# YW_001.net
KiCad netlist of a schematic drawn in Altium Designer
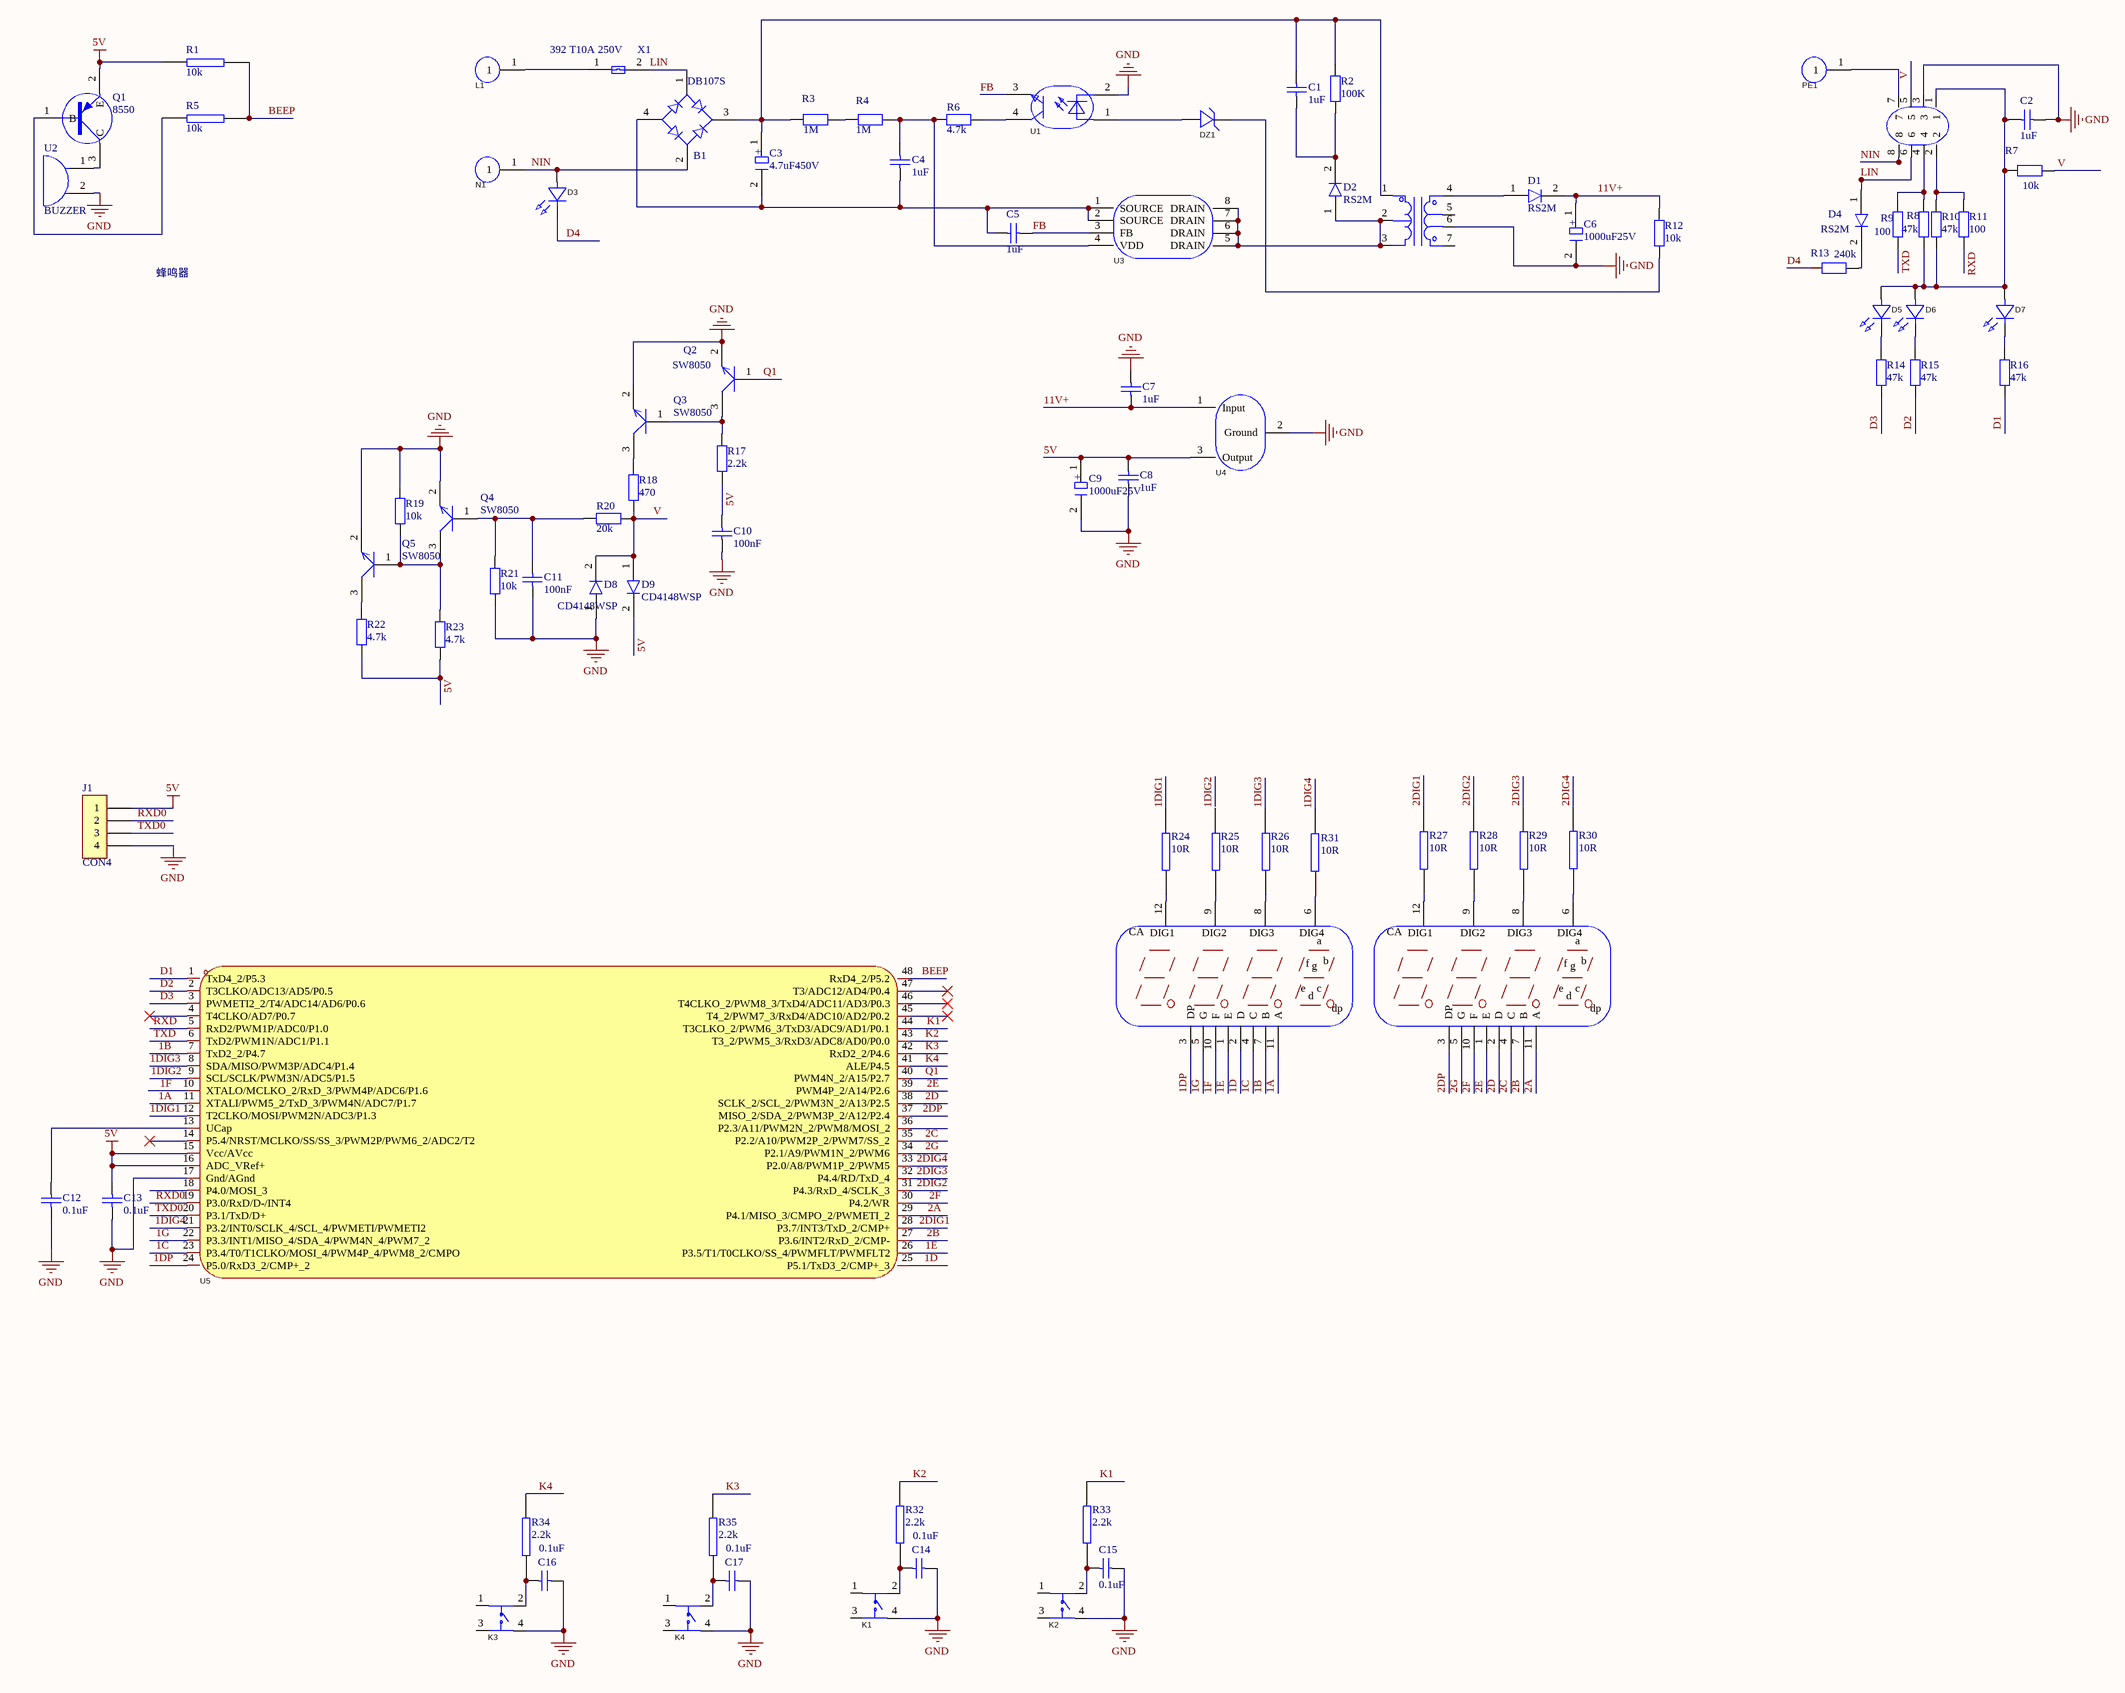
[diagram p0: YW_001.SchDoc]

(export (version "E")
  (design (tool "Eeschema 10.0.6"))
  (components
    (comp (ref "B1") (value "DB107S") (footprint "DB107S") (libsource (lib "*") (part "整流桥堆")))
    (comp (ref "C1")
      (value "1uF")
      (footprint "CAP-TH_L5.5-W4.0-P5.00-D0.5")
      (description "Capacitor")
      (fields (field (name "PUBLISHER") "Altium Limited"))
      (libsource (lib "*") (part "Cap"))
    )
    (comp (ref "C2")
      (value "1uF")
      (footprint "0805C")
      (description "Capacitor")
      (fields (field (name "PUBLISHER") "Altium Limited"))
      (libsource (lib "*") (part "Cap"))
    )
    (comp (ref "C3")
      (value "4.7uF450V")
      (footprint "CAP-TH_BD6.3-P2.50-D1.0-FD")
      (libsource (lib "*") (part "电解电容"))
    )
    (comp (ref "C4")
      (value "1uF")
      (footprint "0805C")
      (description "Capacitor")
      (fields (field (name "PUBLISHER") "Altium Limited"))
      (libsource (lib "*") (part "Cap"))
    )
    (comp (ref "C5")
      (value "1uF")
      (footprint "0805C")
      (description "Capacitor")
      (fields (field (name "PUBLISHER") "Altium Limited"))
      (libsource (lib "*") (part "Cap"))
    )
    (comp (ref "C6")
      (value "1000uF25V")
      (footprint "CAP-TH_BD10.0-P5.00-D1.0-FD")
      (description "CD2881081EM1017VFL")
      (libsource (lib "*") (part "电解电容"))
    )
    (comp (ref "C7")
      (value "1uF")
      (footprint "0805C")
      (description "Capacitor")
      (fields (field (name "PUBLISHER") "Altium Limited"))
      (libsource (lib "*") (part "Cap"))
    )
    (comp (ref "C8")
      (value "1uF")
      (footprint "0805C")
      (description "Capacitor")
      (fields (field (name "PUBLISHER") "Altium Limited"))
      (libsource (lib "*") (part "Cap"))
    )
    (comp (ref "C9")
      (value "1000uF25V")
      (footprint "CAP-TH_BD10.0-P5.00-D1.0-FD")
      (description "CD2881081EM1017VFL")
      (libsource (lib "*") (part "电解电容"))
    )
    (comp (ref "C10")
      (value "100nF")
      (footprint "0805C")
      (description "Capacitor")
      (fields (field (name "PUBLISHER") "Altium Limited"))
      (libsource (lib "*") (part "Cap"))
    )
    (comp (ref "C11")
      (value "100nF")
      (footprint "0805C")
      (description "Capacitor")
      (fields (field (name "PUBLISHER") "Altium Limited"))
      (libsource (lib "*") (part "Cap"))
    )
    (comp (ref "C12")
      (value "0.1uF")
      (footprint "C0603")
      (description "Capacitor")
      (fields (field (name "Comment") "100nF") (field (name "PUBLISHER") "Altium Limited"))
      (libsource (lib "*") (part "Cap"))
    )
    (comp (ref "C13")
      (value "0.1uF")
      (footprint "C0603")
      (description "Capacitor")
      (fields (field (name "Comment") "100nF") (field (name "PUBLISHER") "Altium Limited"))
      (libsource (lib "*") (part "Cap"))
    )
    (comp (ref "C14")
      (value "0.1uF")
      (footprint "0805C")
      (description "Capacitor")
      (fields (field (name "Comment") "104P") (field (name "PUBLISHER") "Altium Limited"))
      (libsource (lib "*") (part "Cap"))
    )
    (comp (ref "C15")
      (value "0.1uF")
      (footprint "0805C")
      (description "Capacitor")
      (fields (field (name "Comment") "104P") (field (name "PUBLISHER") "Altium Limited"))
      (libsource (lib "*") (part "Cap"))
    )
    (comp (ref "C16")
      (value "0.1uF")
      (footprint "0805C")
      (description "Capacitor")
      (fields (field (name "Comment") "104P") (field (name "PUBLISHER") "Altium Limited"))
      (libsource (lib "*") (part "Cap"))
    )
    (comp (ref "C17")
      (value "0.1uF")
      (footprint "0805C")
      (description "Capacitor")
      (fields (field (name "Comment") "104P") (field (name "PUBLISHER") "Altium Limited"))
      (libsource (lib "*") (part "Cap"))
    )
    (comp (ref "D1")
      (value "RS2M")
      (footprint "SMA-SMD_L4.4-W2.7-LS5.4-RD")
      (libsource (lib "CAMERON") (part "二极管"))
    )
    (comp (ref "D2")
      (value "RS2M")
      (footprint "SMA-SMD_L4.4-W2.7-LS5.4-RD")
      (libsource (lib "CAMERON") (part "二极管"))
    )
    (comp (ref "D3")
      (value "HLMP-1503-D0000")
      (footprint "LED-TH_BD3.0-P2.54-RD")
      (fields (field (name "MANUFACTURER") "Broadcom/AVAGO(安华高)"))
      (libsource (lib "CAMERON") (part "HLMP-1503-D0000"))
    )
    (comp (ref "D4")
      (value "RS2M")
      (footprint "SMA-SMD_L4.4-W2.7-LS5.4-RD")
      (libsource (lib "CAMERON") (part "二极管"))
    )
    (comp (ref "D5")
      (value "HLMP-1503-D0000")
      (footprint "LED-TH_BD3.0-P2.54-RD")
      (fields (field (name "MANUFACTURER") "Broadcom/AVAGO(安华高)"))
      (libsource (lib "CAMERON") (part "HLMP-1503-D0000"))
    )
    (comp (ref "D6")
      (value "HLMP-1503-D0000")
      (footprint "LED-TH_BD3.0-P2.54-RD")
      (fields (field (name "MANUFACTURER") "Broadcom/AVAGO(安华高)"))
      (libsource (lib "CAMERON") (part "HLMP-1503-D0000"))
    )
    (comp (ref "D7")
      (value "HLMP-1503-D0000")
      (footprint "LED-TH_BD3.0-P2.54-RD")
      (fields (field (name "MANUFACTURER") "Broadcom/AVAGO(安华高)"))
      (libsource (lib "CAMERON") (part "HLMP-1503-D0000"))
    )
    (comp (ref "D8") (value "CD4148WSP") (footprint "D0805-RD") (libsource (lib "CAMERON") (part "二极管")))
    (comp (ref "D9") (value "CD4148WSP") (footprint "D0805-RD") (libsource (lib "CAMERON") (part "二极管")))
    (comp (ref "DZ1")
      (value "ZMM24")
      (footprint "LL-34_L3.5-W1.5-RD")
      (fields (field (name "MANUFACTURER") "HXY MOSFET(华轩阳电子)"))
      (libsource (lib "CAMERON") (part "ZMM24_C7470923"))
    )
    (comp (ref "H1")
      (value "HC-5557-2*4AW")
      (footprint "CONN-TH_8P-P4.20_5557-2X4AW")
      (fields (field (name "MANUFACTURER") "HCTL(华灿天禄)"))
      (libsource (lib "CAMERON") (part "HC-5557-2*4AW"))
    )
    (comp (ref "J1")
      (value "CON4")
      (footprint "HDR1X4")
      (description "Connector")
      (libsource (lib "*") (part "CON4"))
    )
    (comp (ref "K1")
      (value "TS1212TPFS 250gf 072")
      (footprint "KEY-SMD_4P-L12.0-W12.0-P5.00-LS15.0")
      (fields (field (name "MANUFACTURER") "SHOU HAN(首韩)"))
      (libsource (lib "CAMERON") (part "TS1212TPFS 250gf 072"))
    )
    (comp (ref "K2")
      (value "TS1212TPFS 250gf 072")
      (footprint "KEY-SMD_4P-L12.0-W12.0-P5.00-LS15.0")
      (fields (field (name "MANUFACTURER") "SHOU HAN(首韩)"))
      (libsource (lib "CAMERON") (part "TS1212TPFS 250gf 072"))
    )
    (comp (ref "K3")
      (value "TS1212TPFS 250gf 072")
      (footprint "KEY-SMD_4P-L12.0-W12.0-P5.00-LS15.0")
      (fields (field (name "MANUFACTURER") "SHOU HAN(首韩)"))
      (libsource (lib "CAMERON") (part "TS1212TPFS 250gf 072"))
    )
    (comp (ref "K4")
      (value "TS1212TPFS 250gf 072")
      (footprint "KEY-SMD_4P-L12.0-W12.0-P5.00-LS15.0")
      (fields (field (name "MANUFACTURER") "SHOU HAN(首韩)"))
      (libsource (lib "CAMERON") (part "TS1212TPFS 250gf 072"))
    )
    (comp (ref "L1")
      (value "PZ254V-11-01P")
      (footprint "HDR-TH_1P-P5")
      (fields (field (name "MANUFACTURER") "XFCN(兴飞)"))
      (libsource (lib "CAMERON") (part "PZ254V-11-01P"))
    )
    (comp (ref "LED1")
      (value "FJ5461BH 橙红")
      (footprint "LED-SEG-TH_FJ5461AH")
      (fields (field (name "MANUFACTURER") "志浩"))
      (libsource (lib "CAMERON") (part "FJ5461BH 橙红"))
    )
    (comp (ref "LED2")
      (value "FJ5461BH 橙红")
      (footprint "LED-SEG-TH_FJ5461AH")
      (fields (field (name "MANUFACTURER") "志浩"))
      (libsource (lib "CAMERON") (part "FJ5461BH 橙红"))
    )
    (comp (ref "N1")
      (value "PZ254V-11-01P")
      (footprint "HDR-TH_1P-P5")
      (fields (field (name "MANUFACTURER") "XFCN(兴飞)"))
      (libsource (lib "altium-import") (part "root_2_PZ254V-11-01P_"))
    )
    (comp (ref "PE1")
      (value "PZ254V-11-01P")
      (footprint "HDR-TH_1P-P5")
      (fields (field (name "MANUFACTURER") "XFCN(兴飞)"))
      (libsource (lib "CAMERON") (part "PZ254V-11-01P"))
    )
    (comp (ref "Q1") (value "8550") (footprint "SOT-23") (libsource (lib "*") (part "PNP")))
    (comp (ref "Q2")
      (value "SW8050")
      (footprint "SOT-23 - S8550")
      (libsource (lib "CAMERON") (part "普通三级管（NPN）"))
    )
    (comp (ref "Q3")
      (value "SW8050")
      (footprint "SOT-23 - S8550")
      (libsource (lib "CAMERON") (part "普通三级管（NPN）"))
    )
    (comp (ref "Q4")
      (value "SW8050")
      (footprint "SOT-23 - S8550")
      (libsource (lib "CAMERON") (part "普通三级管（NPN）"))
    )
    (comp (ref "Q5")
      (value "SW8050")
      (footprint "SOT-23 - S8550")
      (libsource (lib "CAMERON") (part "普通三级管（NPN）"))
    )
    (comp (ref "R1") (value "10k") (footprint "0805") (libsource (lib "*") (part "RES2")))
    (comp (ref "R2")
      (value "100K")
      (footprint "0805")
      (description "Resistor")
      (fields (field (name "Comment") "100k") (field (name "PUBLISHER") "Altium Limited"))
      (libsource (lib "*") (part "Res2"))
    )
    (comp (ref "R3")
      (value "1M")
      (footprint "0805")
      (description "Resistor")
      (fields (field (name "PUBLISHER") "Altium Limited"))
      (libsource (lib "") (part "Res2_1"))
    )
    (comp (ref "R4")
      (value "1M")
      (footprint "0805")
      (description "Resistor")
      (fields (field (name "PUBLISHER") "Altium Limited"))
      (libsource (lib "") (part "Res2_1"))
    )
    (comp (ref "R5") (value "10k") (footprint "0805") (libsource (lib "*") (part "RES2")))
    (comp (ref "R6")
      (value "4.7k")
      (footprint "0805")
      (description "Resistor")
      (fields (field (name "PUBLISHER") "Altium Limited"))
      (libsource (lib "") (part "Res2_1"))
    )
    (comp (ref "R7")
      (value "10k")
      (footprint "0805")
      (description "Resistor")
      (fields (field (name "PUBLISHER") "Altium Limited"))
      (libsource (lib "") (part "Res2_1"))
    )
    (comp (ref "R8")
      (value "47k")
      (footprint "0805")
      (description "Resistor")
      (fields (field (name "PUBLISHER") "Altium Limited"))
      (libsource (lib "*") (part "Res2"))
    )
    (comp (ref "R9")
      (value "100")
      (footprint "0805")
      (description "Resistor")
      (fields (field (name "PUBLISHER") "Altium Limited"))
      (libsource (lib "") (part "Res2_2"))
    )
    (comp (ref "R10")
      (value "47k")
      (footprint "0805")
      (description "Resistor")
      (fields (field (name "PUBLISHER") "Altium Limited"))
      (libsource (lib "*") (part "Res2"))
    )
    (comp (ref "R11")
      (value "100")
      (footprint "0805")
      (description "Resistor")
      (fields (field (name "PUBLISHER") "Altium Limited"))
      (libsource (lib "") (part "Res2_2"))
    )
    (comp (ref "R12")
      (value "10k")
      (footprint "0805")
      (description "Resistor")
      (fields (field (name "PUBLISHER") "Altium Limited"))
      (libsource (lib "*") (part "Res2"))
    )
    (comp (ref "R13")
      (value "240k")
      (footprint "0805")
      (description "Resistor")
      (fields (field (name "PUBLISHER") "Altium Limited"))
      (libsource (lib "") (part "Res2_1"))
    )
    (comp (ref "R14")
      (value "47k")
      (footprint "0805")
      (description "Resistor")
      (fields (field (name "PUBLISHER") "Altium Limited"))
      (libsource (lib "*") (part "Res2"))
    )
    (comp (ref "R15")
      (value "47k")
      (footprint "0805")
      (description "Resistor")
      (fields (field (name "PUBLISHER") "Altium Limited"))
      (libsource (lib "*") (part "Res2"))
    )
    (comp (ref "R16")
      (value "47k")
      (footprint "0805")
      (description "Resistor")
      (fields (field (name "PUBLISHER") "Altium Limited"))
      (libsource (lib "*") (part "Res2"))
    )
    (comp (ref "R17")
      (value "2.2k")
      (footprint "0805")
      (description "Resistor")
      (fields (field (name "PUBLISHER") "Altium Limited"))
      (libsource (lib "*") (part "Res2"))
    )
    (comp (ref "R18")
      (value "470")
      (footprint "0805")
      (description "Resistor")
      (fields (field (name "PUBLISHER") "Altium Limited"))
      (libsource (lib "*") (part "Res2"))
    )
    (comp (ref "R19")
      (value "10k")
      (footprint "0805")
      (description "Resistor")
      (fields (field (name "PUBLISHER") "Altium Limited"))
      (libsource (lib "*") (part "Res2"))
    )
    (comp (ref "R20")
      (value "20k")
      (footprint "0805")
      (description "Resistor")
      (fields (field (name "PUBLISHER") "Altium Limited"))
      (libsource (lib "") (part "Res2_3"))
    )
    (comp (ref "R21")
      (value "10k")
      (footprint "0805")
      (description "Resistor")
      (fields (field (name "PUBLISHER") "Altium Limited"))
      (libsource (lib "") (part "Res2_2"))
    )
    (comp (ref "R22")
      (value "4.7k")
      (footprint "0805")
      (description "Resistor")
      (fields (field (name "PUBLISHER") "Altium Limited"))
      (libsource (lib "*") (part "Res2"))
    )
    (comp (ref "R23")
      (value "4.7k")
      (footprint "0805")
      (description "Resistor")
      (fields (field (name "PUBLISHER") "Altium Limited"))
      (libsource (lib "*") (part "Res2"))
    )
    (comp (ref "R24") (value "10R") (footprint "R0603") (libsource (lib "*") (part "RES2")))
    (comp (ref "R25") (value "10R") (footprint "R0603") (libsource (lib "*") (part "RES2")))
    (comp (ref "R26") (value "10R") (footprint "R0603") (libsource (lib "*") (part "RES2")))
    (comp (ref "R27") (value "10R") (footprint "R0603") (libsource (lib "*") (part "RES2")))
    (comp (ref "R28") (value "10R") (footprint "R0603") (libsource (lib "*") (part "RES2")))
    (comp (ref "R29") (value "10R") (footprint "R0603") (libsource (lib "*") (part "RES2")))
    (comp (ref "R30") (value "10R") (footprint "R0603") (libsource (lib "*") (part "RES2")))
    (comp (ref "R31") (value "10R") (footprint "R0603") (libsource (lib "*") (part "RES2")))
    (comp (ref "R32") (value "2.2k") (footprint "0805") (libsource (lib "*") (part "RES2")))
    (comp (ref "R33") (value "2.2k") (footprint "0805") (libsource (lib "*") (part "RES2")))
    (comp (ref "R34") (value "2.2k") (footprint "0805") (libsource (lib "*") (part "RES2")))
    (comp (ref "R35") (value "2.2k") (footprint "0805") (libsource (lib "*") (part "RES2")))
    (comp (ref "U1")
      (value "EL817S1(C)(TU)-F")
      (footprint "OPTO-SMD-4_L4.6-W6.5-P2.54-LS10.3-TL")
      (fields (field (name "MANUFACTURER") "EVERLIGHT(亿光)"))
      (libsource (lib "CAMERON") (part "EL817S1(C)(TU)-F"))
    )
    (comp (ref "U2")
      (value "BUZZER")
      (footprint "BUZZ-7.6/12")
      (description "Buzzer")
      (libsource (lib "*") (part "BUZZER"))
    )
    (comp (ref "U3")
      (value "VIPER12ASTR-E")
      (footprint "SOIC-8_L5.0-W4.0-P1.27-LS6.0-BL")
      (fields (field (name "MANUFACTURER") "ST(意法半导体)"))
      (libsource (lib "CAMERON") (part "VIPER12ASTR-E"))
    )
    (comp (ref "U4")
      (value "MC7805CDTRKG")
      (footprint "TO-252-2_L6.6-W6.1-P4.58-LS9.9-TL")
      (fields (field (name "MANUFACTURER") "onsemi(安森美)"))
      (libsource (lib "CAMERON") (part "MC7805CDTRKG"))
    )
    (comp (ref "U5")
      (value "STC8H8K64U-45I-LQFP48")
      (footprint "LQFP-48_L7.0-W7.0-P0.50-LS9.0-BL")
      (fields (field (name "MANUFACTURER") "STC(宏晶)"))
      (libsource (lib "CAMERON") (part "STC8H8K64U-45I-LQFP48"))
    )
    (comp (ref "USB1")
      (value "ECO2017SEO-X16V015")
      (footprint "XFMR-TH_ECO2017SEO-X16V015")
      (fields (field (name "MANUFACTURER") "TDK"))
      (libsource (lib "CAMERON") (part "ECO2017SEO-X16V015"))
    )
    (comp (ref "X1") (value "392 T10A 250V") (footprint "FUSE") (libsource (lib "*") (part "保险丝")))
  )
  (nets
    (net (code "1") (name "/1A") (class "Default")
      (node (ref "LED1") (pin "11") (pinfunction "A_11") (pintype "passive"))
      (node (ref "U5") (pin "11") (pinfunction "XTALI/PWM5_2/TxD_3/PWM4N/ADC7/P1.7_11") (pintype "passive"))
    )
    (net (code "2") (name "/1B") (class "Default")
      (node (ref "LED1") (pin "7") (pinfunction "B_7") (pintype "passive"))
      (node (ref "U5") (pin "7") (pinfunction "TxD2_2/P4.7_7") (pintype "passive"))
    )
    (net (code "3") (name "/1C") (class "Default")
      (node (ref "LED1") (pin "4") (pinfunction "C_4") (pintype "passive"))
      (node (ref "U5") (pin "23") (pinfunction "P3.4/T0/T1CLKO/MOSI_4/PWM4P_4/PWM8_2/CMPO_23") (pintype "passive"))
    )
    (net (code "4") (name "/1D") (class "Default")
      (node (ref "LED1") (pin "2") (pinfunction "D_2") (pintype "passive"))
      (node (ref "U5") (pin "25") (pinfunction "P5.1/TxD3_2/CMP+_3_25") (pintype "passive"))
    )
    (net (code "5") (name "/1DIG1") (class "Default")
      (node (ref "R24") (pin "1") (pinfunction "1_1") (pintype "passive"))
      (node (ref "U5") (pin "12") (pinfunction "T2CLKO/MOSI/PWM2N/ADC3/P1.3_12") (pintype "passive"))
    )
    (net (code "6") (name "/1DIG2") (class "Default")
      (node (ref "R25") (pin "1") (pinfunction "1_1") (pintype "passive"))
      (node (ref "U5") (pin "9") (pinfunction "SCL/SCLK/PWM3N/ADC5/P1.5_9") (pintype "passive"))
    )
    (net (code "7") (name "/1DIG3") (class "Default")
      (node (ref "R26") (pin "1") (pinfunction "1_1") (pintype "passive"))
      (node (ref "U5") (pin "8") (pinfunction "SDA/MISO/PWM3P/ADC4/P1.4_8") (pintype "passive"))
    )
    (net (code "8") (name "/1DIG4") (class "Default")
      (node (ref "R31") (pin "2") (pinfunction "2_2") (pintype "passive"))
      (node (ref "U5") (pin "21") (pinfunction "P3.2/INT0/SCLK_4/SCL_4/PWMETI/PWMETI2_21") (pintype "passive"))
    )
    (net (code "9") (name "/1DP") (class "Default")
      (node (ref "LED1") (pin "3") (pinfunction "DP_3") (pintype "passive"))
      (node (ref "U5") (pin "24") (pinfunction "P5.0/RxD3_2/CMP+_2_24") (pintype "passive"))
    )
    (net (code "10") (name "/1E") (class "Default")
      (node (ref "LED1") (pin "1") (pinfunction "E_1") (pintype "passive"))
      (node (ref "U5") (pin "26") (pinfunction "P3.5/T1/T0CLKO/SS_4/PWMFLT/PWMFLT2_26") (pintype "passive"))
    )
    (net (code "11") (name "/1F") (class "Default")
      (node (ref "LED1") (pin "10") (pinfunction "F_10") (pintype "passive"))
      (node (ref "U5") (pin "10") (pinfunction "XTALO/MCLKO_2/RxD_3/PWM4P/ADC6/P1.6_10") (pintype "passive"))
    )
    (net (code "12") (name "/1G") (class "Default")
      (node (ref "LED1") (pin "5") (pinfunction "G_5") (pintype "passive"))
      (node (ref "U5") (pin "22") (pinfunction "P3.3/INT1/MISO_4/SDA_4/PWM4N_4/PWM7_2_22") (pintype "passive"))
    )
    (net (code "13") (name "/2A") (class "Default")
      (node (ref "LED2") (pin "11") (pinfunction "A_11") (pintype "passive"))
      (node (ref "U5") (pin "29") (pinfunction "P4.1/MISO_3/CMPO_2/PWMETI_2_29") (pintype "passive"))
    )
    (net (code "14") (name "/2B") (class "Default")
      (node (ref "LED2") (pin "7") (pinfunction "B_7") (pintype "passive"))
      (node (ref "U5") (pin "27") (pinfunction "P3.6/INT2/RxD_2/CMP-_27") (pintype "passive"))
    )
    (net (code "15") (name "/2C") (class "Default")
      (node (ref "LED2") (pin "4") (pinfunction "C_4") (pintype "passive"))
      (node (ref "U5") (pin "35") (pinfunction "P2.2/A10/PWM2P_2/PWM7/SS_2_35") (pintype "passive"))
    )
    (net (code "16") (name "/2D") (class "Default")
      (node (ref "LED2") (pin "2") (pinfunction "D_2") (pintype "passive"))
      (node (ref "U5") (pin "38") (pinfunction "SCLK_2/SCL_2/PWM3N_2/A13/P2.5_38") (pintype "passive"))
    )
    (net (code "17") (name "/2DIG1") (class "Default")
      (node (ref "R27") (pin "1") (pinfunction "1_1") (pintype "passive"))
      (node (ref "U5") (pin "28") (pinfunction "P3.7/INT3/TxD_2/CMP+_28") (pintype "passive"))
    )
    (net (code "18") (name "/2DIG2") (class "Default")
      (node (ref "R28") (pin "1") (pinfunction "1_1") (pintype "passive"))
      (node (ref "U5") (pin "31") (pinfunction "P4.3/RxD_4/SCLK_3_31") (pintype "passive"))
    )
    (net (code "19") (name "/2DIG3") (class "Default")
      (node (ref "R29") (pin "1") (pinfunction "1_1") (pintype "passive"))
      (node (ref "U5") (pin "32") (pinfunction "P4.4/RD/TxD_4_32") (pintype "passive"))
    )
    (net (code "20") (name "/2DIG4") (class "Default")
      (node (ref "R30") (pin "2") (pinfunction "2_2") (pintype "passive"))
      (node (ref "U5") (pin "33") (pinfunction "P2.0/A8/PWM1P_2/PWM5_33") (pintype "passive"))
    )
    (net (code "21") (name "/2DP") (class "Default")
      (node (ref "LED2") (pin "3") (pinfunction "DP_3") (pintype "passive"))
      (node (ref "U5") (pin "37") (pinfunction "MISO_2/SDA_2/PWM3P_2/A12/P2.4_37") (pintype "passive"))
    )
    (net (code "22") (name "/2E") (class "Default")
      (node (ref "LED2") (pin "1") (pinfunction "E_1") (pintype "passive"))
      (node (ref "U5") (pin "39") (pinfunction "PWM4P_2/A14/P2.6_39") (pintype "passive"))
    )
    (net (code "23") (name "/2F") (class "Default")
      (node (ref "LED2") (pin "10") (pinfunction "F_10") (pintype "passive"))
      (node (ref "U5") (pin "30") (pinfunction "P4.2/WR_30") (pintype "passive"))
    )
    (net (code "24") (name "/2G") (class "Default")
      (node (ref "LED2") (pin "5") (pinfunction "G_5") (pintype "passive"))
      (node (ref "U5") (pin "34") (pinfunction "P2.1/A9/PWM1N_2/PWM6_34") (pintype "passive"))
    )
    (net (code "25") (name "/11V+") (class "Default")
      (node (ref "C6") (pin "1") (pintype "passive"))
      (node (ref "C7") (pin "2") (pinfunction "2_2") (pintype "passive"))
      (node (ref "D1") (pin "2") (pintype "passive"))
      (node (ref "R12") (pin "1") (pinfunction "1_1") (pintype "passive"))
      (node (ref "U4") (pin "1") (pinfunction "Input_1") (pintype "passive"))
    )
    (net (code "26") (name "/BEEP") (class "Default")
      (node (ref "R1") (pin "2") (pinfunction "2_2") (pintype "passive"))
      (node (ref "R5") (pin "2") (pinfunction "2_2") (pintype "passive"))
      (node (ref "U5") (pin "48") (pinfunction "RxD4_2/P5.2_48") (pintype "passive"))
    )
    (net (code "27") (name "/D1") (class "Default")
      (node (ref "R16") (pin "2") (pinfunction "2_2") (pintype "passive"))
      (node (ref "U5") (pin "1") (pinfunction "TxD4_2/P5.3_1") (pintype "passive"))
    )
    (net (code "28") (name "/D2") (class "Default")
      (node (ref "R15") (pin "2") (pinfunction "2_2") (pintype "passive"))
      (node (ref "U5") (pin "2") (pinfunction "T3CLKO/ADC13/AD5/P0.5_2") (pintype "passive"))
    )
    (net (code "29") (name "/D3") (class "Default")
      (node (ref "R14") (pin "2") (pinfunction "2_2") (pintype "passive"))
      (node (ref "U5") (pin "3") (pinfunction "PWMETI2_2/T4/ADC14/AD6/P0.6_3") (pintype "passive"))
    )
    (net (code "30") (name "/D4") (class "Default")
      (node (ref "D3") (pin "1") (pinfunction "K_1") (pintype "passive"))
      (node (ref "R13") (pin "2") (pinfunction "2_2") (pintype "passive"))
    )
    (net (code "31") (name "/FB") (class "Default")
      (node (ref "C5") (pin "1") (pinfunction "1_1") (pintype "passive"))
      (node (ref "U1") (pin "3") (pinfunction "EM_3") (pintype "passive"))
      (node (ref "U3") (pin "3") (pinfunction "FB_3") (pintype "passive"))
    )
    (net (code "32") (name "/K1") (class "Default")
      (node (ref "R33") (pin "2") (pinfunction "2_2") (pintype "passive"))
      (node (ref "U5") (pin "44") (pinfunction "T3CLKO_2/PWM6_3/TxD3/ADC9/AD1/P0.1_44") (pintype "passive"))
    )
    (net (code "33") (name "/K2") (class "Default")
      (node (ref "R32") (pin "2") (pinfunction "2_2") (pintype "passive"))
      (node (ref "U5") (pin "43") (pinfunction "T3_2/PWM5_3/RxD3/ADC8/AD0/P0.0_43") (pintype "passive"))
    )
    (net (code "34") (name "/K3") (class "Default")
      (node (ref "R35") (pin "2") (pinfunction "2_2") (pintype "passive"))
      (node (ref "U5") (pin "42") (pinfunction "RxD2_2/P4.6_42") (pintype "passive"))
    )
    (net (code "35") (name "/K4") (class "Default")
      (node (ref "R34") (pin "2") (pinfunction "2_2") (pintype "passive"))
      (node (ref "U5") (pin "41") (pinfunction "ALE/P4.5_41") (pintype "passive"))
    )
    (net (code "36") (name "/LIN") (class "Default")
      (node (ref "B1") (pin "1") (pintype "passive"))
      (node (ref "D4") (pin "1") (pintype "passive"))
      (node (ref "H1") (pin "6") (pinfunction "6_6") (pintype "passive"))
      (node (ref "X1") (pin "2") (pintype "passive"))
    )
    (net (code "37") (name "/NIN") (class "Default")
      (node (ref "B1") (pin "2") (pintype "passive"))
      (node (ref "D3") (pin "2") (pinfunction "A_2") (pintype "passive"))
      (node (ref "H1") (pin "8") (pinfunction "8_8") (pintype "passive"))
      (node (ref "N1") (pin "1") (pinfunction "1_1") (pintype "passive"))
    )
    (net (code "38") (name "/Q1") (class "Default")
      (node (ref "Q2") (pin "1") (pinfunction "B_1") (pintype "passive"))
      (node (ref "U5") (pin "40") (pinfunction "PWM4N_2/A15/P2.7_40") (pintype "passive"))
    )
    (net (code "39") (name "/RXD") (class "Default")
      (node (ref "R11") (pin "1") (pinfunction "1_1") (pintype "passive"))
      (node (ref "U5") (pin "5") (pinfunction "RxD2/PWM1P/ADC0/P1.0_5") (pintype "passive"))
    )
    (net (code "40") (name "/RXD0") (class "Default")
      (node (ref "J1") (pin "2") (pinfunction "2_2") (pintype "passive"))
      (node (ref "U5") (pin "19") (pinfunction "P3.0/RxD/D-/INT4_19") (pintype "passive"))
    )
    (net (code "41") (name "/TXD") (class "Default")
      (node (ref "R9") (pin "1") (pinfunction "1_1") (pintype "passive"))
      (node (ref "U5") (pin "6") (pinfunction "TxD2/PWM1N/ADC1/P1.1_6") (pintype "passive"))
    )
    (net (code "42") (name "/TXD0") (class "Default")
      (node (ref "J1") (pin "3") (pinfunction "3_3") (pintype "passive"))
      (node (ref "U5") (pin "20") (pinfunction "P3.1/TxD/D+_20") (pintype "passive"))
    )
    (net (code "43") (name "/V") (class "Default")
      (node (ref "D8") (pin "2") (pintype "passive"))
      (node (ref "D9") (pin "1") (pintype "passive"))
      (node (ref "H1") (pin "5") (pinfunction "5_5") (pintype "passive"))
      (node (ref "R18") (pin "2") (pinfunction "2_2") (pintype "passive"))
      (node (ref "R20") (pin "2") (pinfunction "2_2") (pintype "passive"))
      (node (ref "R7") (pin "1") (pinfunction "1_1") (pintype "passive"))
    )
    (net (code "44") (name "5V") (class "Default")
      (node (ref "C10") (pin "1") (pinfunction "1_1") (pintype "passive"))
      (node (ref "C13") (pin "2") (pinfunction "2_2") (pintype "passive"))
      (node (ref "C8") (pin "1") (pinfunction "1_1") (pintype "passive"))
      (node (ref "C9") (pin "1") (pintype "passive"))
      (node (ref "D9") (pin "2") (pintype "passive"))
      (node (ref "J1") (pin "1") (pinfunction "1_1") (pintype "passive"))
      (node (ref "Q1") (pin "2") (pinfunction "E_2") (pintype "passive"))
      (node (ref "R1") (pin "1") (pinfunction "1_1") (pintype "passive"))
      (node (ref "R17") (pin "2") (pinfunction "2_2") (pintype "passive"))
      (node (ref "R22") (pin "2") (pinfunction "2_2") (pintype "passive"))
      (node (ref "R23") (pin "2") (pinfunction "2_2") (pintype "passive"))
      (node (ref "U4") (pin "3") (pinfunction "Output_3") (pintype "passive"))
      (node (ref "U5") (pin "15") (pinfunction "Vcc/AVcc_15") (pintype "passive"))
      (node (ref "U5") (pin "16") (pinfunction "ADC_VRef+_16") (pintype "passive"))
    )
    (net (code "45") (name "GND") (class "Default")
      (node (ref "C10") (pin "2") (pinfunction "2_2") (pintype "passive"))
      (node (ref "C11") (pin "2") (pinfunction "2_2") (pintype "passive"))
      (node (ref "C12") (pin "1") (pinfunction "1_1") (pintype "passive"))
      (node (ref "C13") (pin "1") (pinfunction "1_1") (pintype "passive"))
      (node (ref "C14") (pin "2") (pinfunction "2_2") (pintype "passive"))
      (node (ref "C15") (pin "2") (pinfunction "2_2") (pintype "passive"))
      (node (ref "C16") (pin "2") (pinfunction "2_2") (pintype "passive"))
      (node (ref "C17") (pin "2") (pinfunction "2_2") (pintype "passive"))
      (node (ref "C2") (pin "1") (pinfunction "1_1") (pintype "passive"))
      (node (ref "C6") (pin "2") (pintype "passive"))
      (node (ref "C7") (pin "1") (pinfunction "1_1") (pintype "passive"))
      (node (ref "C8") (pin "2") (pinfunction "2_2") (pintype "passive"))
      (node (ref "C9") (pin "2") (pintype "passive"))
      (node (ref "D8") (pin "1") (pintype "passive"))
      (node (ref "H1") (pin "3") (pinfunction "3_3") (pintype "passive"))
      (node (ref "J1") (pin "4") (pinfunction "4_4") (pintype "passive"))
      (node (ref "K1") (pin "4") (pinfunction "4_4") (pintype "passive"))
      (node (ref "K2") (pin "4") (pinfunction "4_4") (pintype "passive"))
      (node (ref "K3") (pin "4") (pinfunction "4_4") (pintype "passive"))
      (node (ref "K4") (pin "4") (pinfunction "4_4") (pintype "passive"))
      (node (ref "Q2") (pin "2") (pinfunction "E_2") (pintype "passive"))
      (node (ref "Q3") (pin "2") (pinfunction "E_2") (pintype "passive"))
      (node (ref "Q4") (pin "2") (pinfunction "E_2") (pintype "passive"))
      (node (ref "Q5") (pin "2") (pinfunction "E_2") (pintype "passive"))
      (node (ref "R19") (pin "1") (pinfunction "1_1") (pintype "passive"))
      (node (ref "R21") (pin "1") (pinfunction "1_1") (pintype "passive"))
      (node (ref "U1") (pin "2") (pinfunction "CAT_2") (pintype "passive"))
      (node (ref "U2") (pin "2") (pinfunction "B_2") (pintype "passive"))
      (node (ref "U4") (pin "2") (pinfunction "Ground_2") (pintype "passive"))
      (node (ref "U5") (pin "17") (pinfunction "Gnd/AGnd_17") (pintype "passive"))
      (node (ref "USB1") (pin "6") (pinfunction "2_6") (pintype "passive"))
    )
    (net (code "46") (name "Net-(B1-Pad4)") (class "Default")
      (node (ref "B1") (pin "4") (pintype "passive"))
      (node (ref "C3") (pin "2") (pintype "passive"))
      (node (ref "C4") (pin "2") (pinfunction "2_2") (pintype "passive"))
      (node (ref "C5") (pin "2") (pinfunction "2_2") (pintype "passive"))
      (node (ref "U3") (pin "1") (pinfunction "SOURCE_1") (pintype "passive"))
      (node (ref "U3") (pin "2") (pinfunction "SOURCE_2") (pintype "passive"))
    )
    (net (code "47") (name "Net-(C1-Pad2)") (class "Default")
      (node (ref "C1") (pin "2") (pinfunction "2_2") (pintype "passive"))
      (node (ref "D2") (pin "2") (pintype "passive"))
      (node (ref "R2") (pin "2") (pinfunction "2_2") (pintype "passive"))
    )
    (net (code "48") (name "Net-(C14-Pad1)") (class "Default")
      (node (ref "C14") (pin "1") (pinfunction "1_1") (pintype "passive"))
      (node (ref "K1") (pin "2") (pinfunction "2_2") (pintype "passive"))
      (node (ref "R32") (pin "1") (pinfunction "1_1") (pintype "passive"))
    )
    (net (code "49") (name "Net-(C15-Pad1)") (class "Default")
      (node (ref "C15") (pin "1") (pinfunction "1_1") (pintype "passive"))
      (node (ref "K2") (pin "2") (pinfunction "2_2") (pintype "passive"))
      (node (ref "R33") (pin "1") (pinfunction "1_1") (pintype "passive"))
    )
    (net (code "50") (name "Net-(C16-Pad1)") (class "Default")
      (node (ref "C16") (pin "1") (pinfunction "1_1") (pintype "passive"))
      (node (ref "K3") (pin "2") (pinfunction "2_2") (pintype "passive"))
      (node (ref "R34") (pin "1") (pinfunction "1_1") (pintype "passive"))
    )
    (net (code "51") (name "Net-(C17-Pad1)") (class "Default")
      (node (ref "C17") (pin "1") (pinfunction "1_1") (pintype "passive"))
      (node (ref "K4") (pin "2") (pinfunction "2_2") (pintype "passive"))
      (node (ref "R35") (pin "1") (pinfunction "1_1") (pintype "passive"))
    )
    (net (code "52") (name "Net-(D4-Pad2)") (class "Default")
      (node (ref "D4") (pin "2") (pintype "passive"))
      (node (ref "R13") (pin "1") (pinfunction "1_1") (pintype "passive"))
    )
    (net (code "53") (name "Net-(D5-A)") (class "Default")
      (node (ref "C2") (pin "2") (pinfunction "2_2") (pintype "passive"))
      (node (ref "D5") (pin "2") (pinfunction "A_2") (pintype "passive"))
      (node (ref "D6") (pin "2") (pinfunction "A_2") (pintype "passive"))
      (node (ref "D7") (pin "2") (pinfunction "A_2") (pintype "passive"))
      (node (ref "H1") (pin "1") (pinfunction "1_1") (pintype "passive"))
      (node (ref "R10") (pin "2") (pinfunction "2_2") (pintype "passive"))
      (node (ref "R7") (pin "2") (pinfunction "2_2") (pintype "passive"))
      (node (ref "R8") (pin "2") (pinfunction "2_2") (pintype "passive"))
    )
    (net (code "54") (name "Net-(D5-K)") (class "Default")
      (node (ref "D5") (pin "1") (pinfunction "K_1") (pintype "passive"))
      (node (ref "R14") (pin "1") (pinfunction "1_1") (pintype "passive"))
    )
    (net (code "55") (name "Net-(D6-K)") (class "Default")
      (node (ref "D6") (pin "1") (pinfunction "K_1") (pintype "passive"))
      (node (ref "R15") (pin "1") (pinfunction "1_1") (pintype "passive"))
    )
    (net (code "56") (name "Net-(D7-K)") (class "Default")
      (node (ref "D7") (pin "1") (pinfunction "K_1") (pintype "passive"))
      (node (ref "R16") (pin "1") (pinfunction "1_1") (pintype "passive"))
    )
    (net (code "57") (name "Net-(DZ1-A)") (class "Default")
      (node (ref "DZ1") (pin "2") (pinfunction "A_2") (pintype "passive"))
      (node (ref "U1") (pin "1") (pinfunction "AN_1") (pintype "passive"))
    )
    (net (code "58") (name "Net-(DZ1-C)") (class "Default")
      (node (ref "DZ1") (pin "1") (pinfunction "C_1") (pintype "passive"))
      (node (ref "R12") (pin "2") (pinfunction "2_2") (pintype "passive"))
    )
    (net (code "59") (name "Net-(H1-Pad2)") (class "Default")
      (node (ref "H1") (pin "2") (pinfunction "2_2") (pintype "passive"))
      (node (ref "R10") (pin "1") (pinfunction "1_1") (pintype "passive"))
      (node (ref "R11") (pin "2") (pinfunction "2_2") (pintype "passive"))
    )
    (net (code "60") (name "Net-(H1-Pad4)") (class "Default")
      (node (ref "H1") (pin "4") (pinfunction "4_4") (pintype "passive"))
      (node (ref "R8") (pin "1") (pinfunction "1_1") (pintype "passive"))
      (node (ref "R9") (pin "2") (pinfunction "2_2") (pintype "passive"))
    )
    (net (code "61") (name "Net-(H1-Pad7)") (class "Default")
      (node (ref "H1") (pin "7") (pinfunction "7_7") (pintype "passive"))
      (node (ref "PE1") (pin "1") (pinfunction "1_1") (pintype "passive"))
    )
    (net (code "62") (name "Net-(L1-Pad1)") (class "Default")
      (node (ref "L1") (pin "1") (pinfunction "1_1") (pintype "passive"))
      (node (ref "X1") (pin "1") (pintype "passive"))
    )
    (net (code "63") (name "Net-(LED1-DIG1)") (class "Default")
      (node (ref "LED1") (pin "12") (pinfunction "DIG1_12") (pintype "passive"))
      (node (ref "R24") (pin "2") (pinfunction "2_2") (pintype "passive"))
    )
    (net (code "64") (name "Net-(LED1-DIG2)") (class "Default")
      (node (ref "LED1") (pin "9") (pinfunction "DIG2_9") (pintype "passive"))
      (node (ref "R25") (pin "2") (pinfunction "2_2") (pintype "passive"))
    )
    (net (code "65") (name "Net-(LED1-DIG3)") (class "Default")
      (node (ref "LED1") (pin "8") (pinfunction "DIG3_8") (pintype "passive"))
      (node (ref "R26") (pin "2") (pinfunction "2_2") (pintype "passive"))
    )
    (net (code "66") (name "Net-(LED1-DIG4)") (class "Default")
      (node (ref "LED1") (pin "6") (pinfunction "DIG4_6") (pintype "passive"))
      (node (ref "R31") (pin "1") (pinfunction "1_1") (pintype "passive"))
    )
    (net (code "67") (name "Net-(LED2-DIG1)") (class "Default")
      (node (ref "LED2") (pin "12") (pinfunction "DIG1_12") (pintype "passive"))
      (node (ref "R27") (pin "2") (pinfunction "2_2") (pintype "passive"))
    )
    (net (code "68") (name "Net-(LED2-DIG2)") (class "Default")
      (node (ref "LED2") (pin "9") (pinfunction "DIG2_9") (pintype "passive"))
      (node (ref "R28") (pin "2") (pinfunction "2_2") (pintype "passive"))
    )
    (net (code "69") (name "Net-(LED2-DIG3)") (class "Default")
      (node (ref "LED2") (pin "8") (pinfunction "DIG3_8") (pintype "passive"))
      (node (ref "R29") (pin "2") (pinfunction "2_2") (pintype "passive"))
    )
    (net (code "70") (name "Net-(LED2-DIG4)") (class "Default")
      (node (ref "LED2") (pin "6") (pinfunction "DIG4_6") (pintype "passive"))
      (node (ref "R30") (pin "1") (pinfunction "1_1") (pintype "passive"))
    )
    (net (code "71") (name "Net-(Q1-B)") (class "Default")
      (node (ref "Q1") (pin "1") (pinfunction "B_1") (pintype "passive"))
      (node (ref "R5") (pin "1") (pinfunction "1_1") (pintype "passive"))
    )
    (net (code "72") (name "Net-(Q1-C)") (class "Default")
      (node (ref "Q1") (pin "3") (pinfunction "C_3") (pintype "passive"))
      (node (ref "U2") (pin "1") (pinfunction "A_1") (pintype "passive"))
    )
    (net (code "73") (name "Net-(Q2-C)") (class "Default")
      (node (ref "Q2") (pin "3") (pinfunction "C_3") (pintype "passive"))
      (node (ref "Q3") (pin "1") (pinfunction "B_1") (pintype "passive"))
      (node (ref "R17") (pin "1") (pinfunction "1_1") (pintype "passive"))
    )
    (net (code "74") (name "Net-(Q3-C)") (class "Default")
      (node (ref "Q3") (pin "3") (pinfunction "C_3") (pintype "passive"))
      (node (ref "R18") (pin "1") (pinfunction "1_1") (pintype "passive"))
    )
    (net (code "75") (name "Net-(Q4-B)") (class "Default")
      (node (ref "C11") (pin "1") (pinfunction "1_1") (pintype "passive"))
      (node (ref "Q4") (pin "1") (pinfunction "B_1") (pintype "passive"))
      (node (ref "R20") (pin "1") (pinfunction "1_1") (pintype "passive"))
      (node (ref "R21") (pin "2") (pinfunction "2_2") (pintype "passive"))
    )
    (net (code "76") (name "Net-(Q4-C)") (class "Default")
      (node (ref "Q4") (pin "3") (pinfunction "C_3") (pintype "passive"))
      (node (ref "Q5") (pin "1") (pinfunction "B_1") (pintype "passive"))
      (node (ref "R19") (pin "2") (pinfunction "2_2") (pintype "passive"))
      (node (ref "R23") (pin "1") (pinfunction "1_1") (pintype "passive"))
    )
    (net (code "77") (name "Net-(Q5-C)") (class "Default")
      (node (ref "Q5") (pin "3") (pinfunction "C_3") (pintype "passive"))
      (node (ref "R22") (pin "1") (pinfunction "1_1") (pintype "passive"))
    )
    (net (code "78") (name "Net-(R3-Pad1)") (class "Default")
      (node (ref "R3") (pin "1") (pinfunction "1_1") (pintype "passive"))
      (node (ref "R4") (pin "2") (pinfunction "2_2") (pintype "passive"))
    )
    (net (code "79") (name "Net-(U1-COL)") (class "Default")
      (node (ref "R6") (pin "1") (pinfunction "1_1") (pintype "passive"))
      (node (ref "U1") (pin "4") (pinfunction "COL_4") (pintype "passive"))
    )
    (net (code "80") (name "Net-(U3-VDD)") (class "Default")
      (node (ref "C4") (pin "1") (pinfunction "1_1") (pintype "passive"))
      (node (ref "R4") (pin "1") (pinfunction "1_1") (pintype "passive"))
      (node (ref "R6") (pin "2") (pinfunction "2_2") (pintype "passive"))
      (node (ref "U3") (pin "4") (pinfunction "VDD_4") (pintype "passive"))
    )
    (net (code "81") (name "Net-(U5-UCap)") (class "Default")
      (node (ref "C12") (pin "2") (pinfunction "2_2") (pintype "passive"))
      (node (ref "U5") (pin "13") (pinfunction "UCap_13") (pintype "passive"))
    )
    (net (code "82") (name "Net-(USB1-5)") (class "Default")
      (node (ref "D1") (pin "1") (pintype "passive"))
      (node (ref "USB1") (pin "4") (pinfunction "5_4") (pintype "passive"))
    )
    (net (code "83") (name "Net-(USB1-9)") (class "Default")
      (node (ref "B1") (pin "3") (pintype "passive"))
      (node (ref "C1") (pin "1") (pinfunction "1_1") (pintype "passive"))
      (node (ref "C3") (pin "1") (pintype "passive"))
      (node (ref "R2") (pin "1") (pinfunction "1_1") (pintype "passive"))
      (node (ref "R3") (pin "2") (pinfunction "2_2") (pintype "passive"))
      (node (ref "USB1") (pin "1") (pinfunction "9_1") (pintype "passive"))
    )
    (net (code "84") (name "Net-(USB1-10)") (class "Default")
      (node (ref "D2") (pin "1") (pintype "passive"))
      (node (ref "U3") (pin "5") (pinfunction "DRAIN_5") (pintype "passive"))
      (node (ref "U3") (pin "6") (pinfunction "DRAIN_6") (pintype "passive"))
      (node (ref "U3") (pin "7") (pinfunction "DRAIN_7") (pintype "passive"))
      (node (ref "U3") (pin "8") (pinfunction "DRAIN_8") (pintype "passive"))
      (node (ref "USB1") (pin "2") (pinfunction "8_2") (pintype "passive"))
      (node (ref "USB1") (pin "3") (pinfunction "10_3") (pintype "passive"))
    )
    (net (code "85") (name "unconnected-(K1-Pad1)") (class "Default")
      (node (ref "K1") (pin "1") (pinfunction "1_1") (pintype "passive"))
    )
    (net (code "86") (name "unconnected-(K1-Pad3)") (class "Default")
      (node (ref "K1") (pin "3") (pinfunction "3_3") (pintype "passive"))
    )
    (net (code "87") (name "unconnected-(K2-Pad1)") (class "Default")
      (node (ref "K2") (pin "1") (pinfunction "1_1") (pintype "passive"))
    )
    (net (code "88") (name "unconnected-(K2-Pad3)") (class "Default")
      (node (ref "K2") (pin "3") (pinfunction "3_3") (pintype "passive"))
    )
    (net (code "89") (name "unconnected-(K3-Pad1)") (class "Default")
      (node (ref "K3") (pin "1") (pinfunction "1_1") (pintype "passive"))
    )
    (net (code "90") (name "unconnected-(K3-Pad3)") (class "Default")
      (node (ref "K3") (pin "3") (pinfunction "3_3") (pintype "passive"))
    )
    (net (code "91") (name "unconnected-(K4-Pad1)") (class "Default")
      (node (ref "K4") (pin "1") (pinfunction "1_1") (pintype "passive"))
    )
    (net (code "92") (name "unconnected-(K4-Pad3)") (class "Default")
      (node (ref "K4") (pin "3") (pinfunction "3_3") (pintype "passive"))
    )
    (net (code "93") (name "unconnected-(U5-P2.3{slash}A11{slash}PWM2N_2{slash}PWM8{slash}MOSI_2-Pad36)") (class "Default")
      (node (ref "U5") (pin "36") (pinfunction "P2.3/A11/PWM2N_2/PWM8/MOSI_2_36") (pintype "passive"))
    )
    (net (code "94") (name "unconnected-(U5-P4.0{slash}MOSI_3-Pad18)") (class "Default")
      (node (ref "U5") (pin "18") (pinfunction "P4.0/MOSI_3_18") (pintype "passive"))
    )
    (net (code "95") (name "unconnected-(U5-P5.4{slash}NRST{slash}MCLKO{slash}SS{slash}SS_3{slash}PWM2P{slash}PWM6_2{slash}ADC2{slash}T2-Pad14)") (class "Default")
      (node (ref "U5") (pin "14") (pinfunction "P5.4/NRST/MCLKO/SS/SS_3/PWM2P/PWM6_2/ADC2/T2_14") (pintype "passive+no_connect"))
    )
    (net (code "96") (name "unconnected-(U5-T3{slash}ADC12{slash}AD4{slash}P0.4-Pad47)") (class "Default")
      (node (ref "U5") (pin "47") (pinfunction "T3/ADC12/AD4/P0.4_47") (pintype "passive+no_connect"))
    )
    (net (code "97") (name "unconnected-(U5-T4CLKO_2{slash}PWM8_3{slash}TxD4{slash}ADC11{slash}AD3{slash}P0.3-Pad46)") (class "Default")
      (node (ref "U5") (pin "46") (pinfunction "T4CLKO_2/PWM8_3/TxD4/ADC11/AD3/P0.3_46") (pintype "passive+no_connect"))
    )
    (net (code "98") (name "unconnected-(U5-T4CLKO{slash}AD7{slash}P0.7-Pad4)") (class "Default")
      (node (ref "U5") (pin "4") (pinfunction "T4CLKO/AD7/P0.7_4") (pintype "passive+no_connect"))
    )
    (net (code "99") (name "unconnected-(U5-T4_2{slash}PWM7_3{slash}RxD4{slash}ADC10{slash}AD2{slash}P0.2-Pad45)") (class "Default")
      (node (ref "U5") (pin "45") (pinfunction "T4_2/PWM7_3/RxD4/ADC10/AD2/P0.2_45") (pintype "passive+no_connect"))
    )
    (net (code "100") (name "unconnected-(USB1-1-Pad7)") (class "Default")
      (node (ref "USB1") (pin "7") (pinfunction "1_7") (pintype "passive"))
    )
    (net (code "101") (name "unconnected-(USB1-4-Pad5)") (class "Default")
      (node (ref "USB1") (pin "5") (pinfunction "4_5") (pintype "passive"))
    )
  )
)
